# actuators.net
KiCad netlist of a schematic drawn in Altium Designer
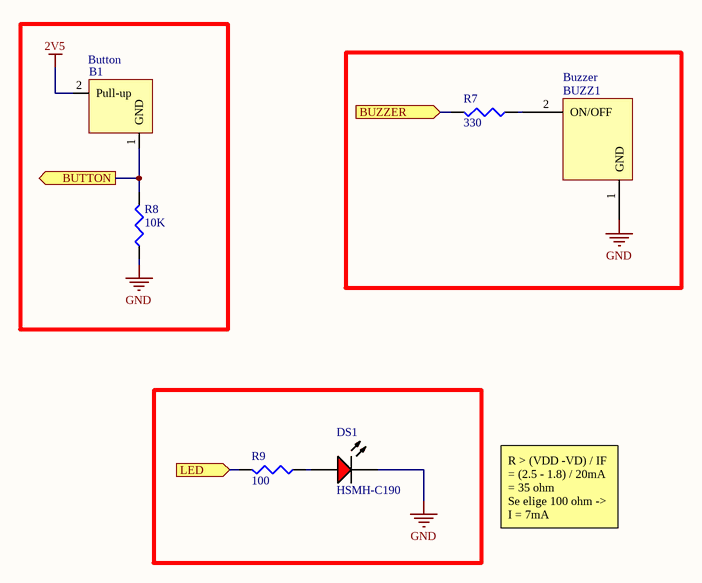
[diagram p0: actuators.SchDoc]

(export (version "E")
  (design (tool "Eeschema 10.0.6"))
  (components
    (comp (ref "B1") (value "Button") (footprint "Button") (libsource (lib "DEOP2023") (part "Button")))
    (comp (ref "BUZZ1")
      (value "Buzzer")
      (footprint "SOP_Buzzer")
      (libsource (lib "DEOP2023") (part "Buzzer"))
    )
    (comp (ref "DS1")
      (value "HSMH-C190")
      (footprint "AVAG-HSMX-C190_V")
      (description "LED Uni-Color Red, 65 mW, 20 mA, -40 to 85 degC, 2-Pin SMD, RoHS, Tape and Reel")
      (libsource (lib "Components - 22.03.23 - 13.02") (part "CMP-1744-00004-1"))
    )
    (comp (ref "R7")
      (value "330")
      (footprint "J1-0603")
      (description "Resistor")
      (fields (field (name "Comment") "Res3") (field (name "PUBLISHER") "Altium Limited"))
      (libsource (lib "Miscellaneous Devices") (part "Res3"))
    )
    (comp (ref "R8")
      (value "10K")
      (footprint "J1-0603")
      (description "Resistor")
      (fields (field (name "Comment") "Res3") (field (name "PUBLISHER") "Altium Limited"))
      (libsource (lib "Miscellaneous Devices") (part "Res3"))
    )
    (comp (ref "R9")
      (value "100")
      (footprint "J1-0603")
      (description "Resistor")
      (fields (field (name "Comment") "Res3") (field (name "PUBLISHER") "Altium Limited"))
      (libsource (lib "Miscellaneous Devices") (part "Res3"))
    )
  )
  (nets
    (net (code "1") (name "/BUTTON") (class "Default")
      (node (ref "B1") (pin "1") (pinfunction "GND_1") (pintype "open_collector"))
      (node (ref "R8") (pin "2") (pinfunction "2_2") (pintype "passive"))
    )
    (net (code "2") (name "/BUZZER") (class "Default")
      (node (ref "R7") (pin "2") (pinfunction "2_2") (pintype "passive"))
    )
    (net (code "3") (name "/LED") (class "Default")
      (node (ref "R9") (pin "2") (pinfunction "2_2") (pintype "passive"))
    )
    (net (code "4") (name "2V5") (class "Default")
      (node (ref "B1") (pin "2") (pinfunction "Pull-up_2") (pintype "power_in"))
    )
    (net (code "5") (name "GND") (class "Default")
      (node (ref "BUZZ1") (pin "1") (pinfunction "GND_1") (pintype "power_in"))
      (node (ref "DS1") (pin "2") (pinfunction "K_2") (pintype "passive"))
      (node (ref "R8") (pin "1") (pinfunction "1_1") (pintype "passive"))
    )
    (net (code "6") (name "Net-(BUZZ1-ON{slash}OFF)") (class "Default")
      (node (ref "BUZZ1") (pin "2") (pinfunction "ON/OFF_2") (pintype "passive"))
      (node (ref "R7") (pin "1") (pinfunction "1_1") (pintype "passive"))
    )
    (net (code "7") (name "Net-(DS1-A)") (class "Default")
      (node (ref "DS1") (pin "1") (pinfunction "A_1") (pintype "passive"))
      (node (ref "R9") (pin "1") (pinfunction "1_1") (pintype "passive"))
    )
  )
)
